# display-board.net
KiCad netlist of a schematic drawn in Altium Designer
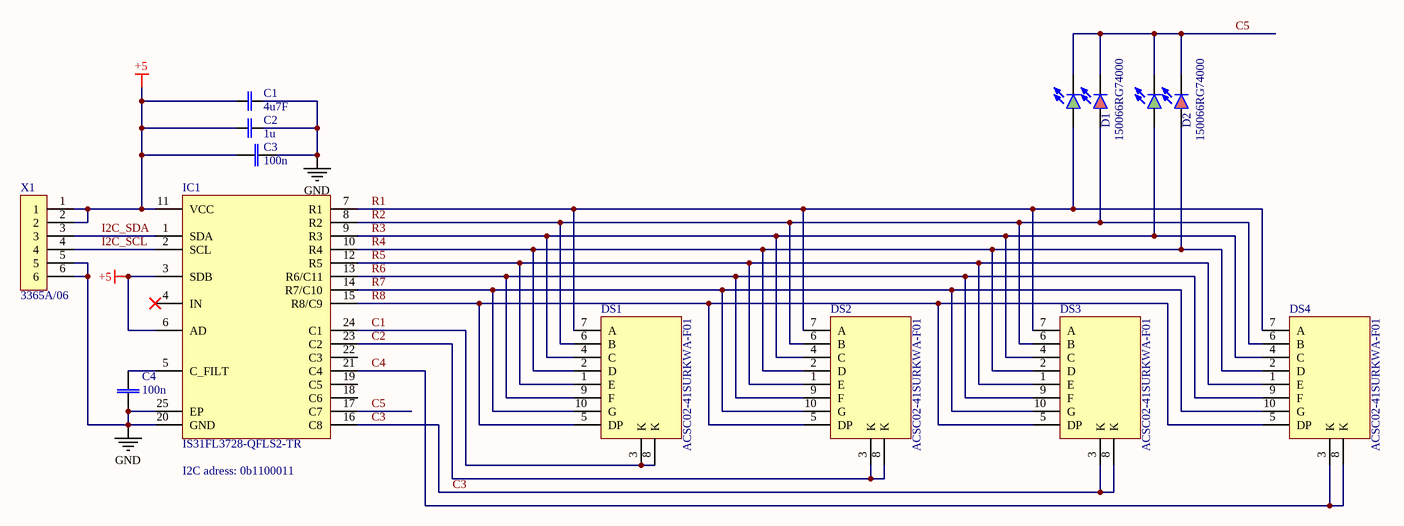
[diagram p0: display-board.SchDoc]

(export (version "E")
  (design (tool "Eeschema 10.0.6"))
  (components
    (comp (ref "C1")
      (value "4u7F")
      (footprint "0805")
      (fields (field (name "PART NUMBER") "000090"))
      (libsource (lib "TychosLibrary") (part "Capacitor"))
    )
    (comp (ref "C2")
      (value "1u")
      (footprint "0603")
      (fields (field (name "PART NUMBER") "000088"))
      (libsource (lib "TychosLibrary") (part "Capacitor"))
    )
    (comp (ref "C3")
      (value "100n")
      (footprint "CAP0402")
      (fields (field (name "MPN") "CL05A104KA5NNNC") (field (name "TOLERANCE") "10%"))
      (libsource (lib "Passive") (part "CL05A104KA5NNNC"))
    )
    (comp (ref "C4")
      (value "100n")
      (footprint "CAP0402")
      (fields (field (name "MPN") "CL05A104KA5NNNC") (field (name "TOLERANCE") "10%"))
      (libsource (lib "Passive") (part "CL05A104KA5NNNC"))
    )
    (comp (ref "D1")
      (value "150066RG74000")
      (footprint "150066RG74000")
      (description "Grün, Rot 520nm Grün, 625nm Rot LED-Indikator - Diskret 3,2V Grün, 2V Rot 0606 (1616 metrisch)")
      (libsource (lib "Schematic") (part "150066RG74000"))
    )
    (comp (ref "D2")
      (value "150066RG74000")
      (footprint "150066RG74000")
      (description "Grün, Rot 520nm Grün, 625nm Rot LED-Indikator - Diskret 3,2V Grün, 2V Rot 0606 (1616 metrisch)")
      (libsource (lib "Schematic") (part "150066RG74000"))
    )
    (comp (ref "DS1")
      (value "ACSC02-41SURKWA-F01")
      (footprint "ACSC02-41SURKWA-F01")
      (libsource (lib "Schematic") (part "ACSC02-41SURKWA-F01"))
    )
    (comp (ref "DS2")
      (value "ACSC02-41SURKWA-F01")
      (footprint "ACSC02-41SURKWA-F01")
      (libsource (lib "Schematic") (part "ACSC02-41SURKWA-F01"))
    )
    (comp (ref "DS3")
      (value "ACSC02-41SURKWA-F01")
      (footprint "ACSC02-41SURKWA-F01")
      (libsource (lib "Schematic") (part "ACSC02-41SURKWA-F01"))
    )
    (comp (ref "DS4")
      (value "ACSC02-41SURKWA-F01")
      (footprint "ACSC02-41SURKWA-F01")
      (libsource (lib "Schematic") (part "ACSC02-41SURKWA-F01"))
    )
    (comp (ref "IC1")
      (value "IS31FL3728-QFLS2-TR")
      (footprint "QFN24_4X4(IS31FL3728)")
      (libsource (lib "Schematic") (part "IS31FL3728-QFLS2-TR"))
    )
    (comp (ref "X1")
      (value "3365A/06")
      (footprint "3M_CBL_RIBN_6X")
      (libsource (lib "Schematic") (part "3365A/06"))
    )
  )
  (nets
    (net (code "1") (name "+5") (class "Default")
      (node (ref "C1") (pin "2") (pinfunction "2_2") (pintype "passive"))
      (node (ref "C2") (pin "2") (pinfunction "2_2") (pintype "passive"))
      (node (ref "C3") (pin "2") (pinfunction "2_2") (pintype "passive"))
      (node (ref "IC1") (pin "11") (pinfunction "VCC_11") (pintype "passive"))
      (node (ref "IC1") (pin "3") (pinfunction "SDB_3") (pintype "passive"))
      (node (ref "IC1") (pin "6") (pinfunction "AD_6") (pintype "passive"))
      (node (ref "X1") (pin "1") (pinfunction "1_1") (pintype "passive"))
      (node (ref "X1") (pin "2") (pinfunction "2_2") (pintype "passive"))
    )
    (net (code "2") (name "/C1") (class "Default")
      (node (ref "DS1") (pin "3") (pinfunction "K_3") (pintype "passive"))
      (node (ref "DS1") (pin "8") (pinfunction "K_8") (pintype "passive"))
      (node (ref "IC1") (pin "24") (pinfunction "C1_24") (pintype "passive"))
    )
    (net (code "3") (name "/C2") (class "Default")
      (node (ref "DS2") (pin "3") (pinfunction "K_3") (pintype "passive"))
      (node (ref "DS2") (pin "8") (pinfunction "K_8") (pintype "passive"))
      (node (ref "IC1") (pin "23") (pinfunction "C2_23") (pintype "passive"))
    )
    (net (code "4") (name "/C3") (class "Default")
      (node (ref "DS3") (pin "3") (pinfunction "K_3") (pintype "passive"))
      (node (ref "DS3") (pin "8") (pinfunction "K_8") (pintype "passive"))
      (node (ref "IC1") (pin "16") (pinfunction "C8_16") (pintype "passive"))
    )
    (net (code "5") (name "/C4") (class "Default")
      (node (ref "DS4") (pin "3") (pinfunction "K_3") (pintype "passive"))
      (node (ref "DS4") (pin "8") (pinfunction "K_8") (pintype "passive"))
      (node (ref "IC1") (pin "21") (pinfunction "C4_21") (pintype "passive"))
    )
    (net (code "6") (name "/C5") (class "Default")
      (node (ref "D1") (pin "1") (pinfunction "1_1") (pintype "passive"))
      (node (ref "D1") (pin "2") (pinfunction "2_2") (pintype "passive"))
      (node (ref "D2") (pin "1") (pinfunction "1_1") (pintype "passive"))
      (node (ref "D2") (pin "2") (pinfunction "2_2") (pintype "passive"))
      (node (ref "IC1") (pin "17") (pinfunction "C7_17") (pintype "passive"))
    )
    (net (code "7") (name "/I2C_SCL") (class "Default")
      (node (ref "IC1") (pin "2") (pinfunction "SCL_2") (pintype "passive"))
      (node (ref "X1") (pin "4") (pinfunction "4_4") (pintype "passive"))
    )
    (net (code "8") (name "/I2C_SDA") (class "Default")
      (node (ref "IC1") (pin "1") (pinfunction "SDA_1") (pintype "passive"))
      (node (ref "X1") (pin "3") (pinfunction "3_3") (pintype "passive"))
    )
    (net (code "9") (name "/R1") (class "Default")
      (node (ref "D1") (pin "3") (pinfunction "3_3") (pintype "passive"))
      (node (ref "DS1") (pin "7") (pinfunction "A_7") (pintype "passive"))
      (node (ref "DS2") (pin "7") (pinfunction "A_7") (pintype "passive"))
      (node (ref "DS3") (pin "7") (pinfunction "A_7") (pintype "passive"))
      (node (ref "DS4") (pin "7") (pinfunction "A_7") (pintype "passive"))
      (node (ref "IC1") (pin "7") (pinfunction "R1_7") (pintype "passive"))
    )
    (net (code "10") (name "/R2") (class "Default")
      (node (ref "D1") (pin "4") (pinfunction "4_4") (pintype "passive"))
      (node (ref "DS1") (pin "6") (pinfunction "B_6") (pintype "passive"))
      (node (ref "DS2") (pin "6") (pinfunction "B_6") (pintype "passive"))
      (node (ref "DS3") (pin "6") (pinfunction "B_6") (pintype "passive"))
      (node (ref "DS4") (pin "6") (pinfunction "B_6") (pintype "passive"))
      (node (ref "IC1") (pin "8") (pinfunction "R2_8") (pintype "passive"))
    )
    (net (code "11") (name "/R3") (class "Default")
      (node (ref "D2") (pin "3") (pinfunction "3_3") (pintype "passive"))
      (node (ref "DS1") (pin "4") (pinfunction "C_4") (pintype "passive"))
      (node (ref "DS2") (pin "4") (pinfunction "C_4") (pintype "passive"))
      (node (ref "DS3") (pin "4") (pinfunction "C_4") (pintype "passive"))
      (node (ref "DS4") (pin "4") (pinfunction "C_4") (pintype "passive"))
      (node (ref "IC1") (pin "9") (pinfunction "R3_9") (pintype "passive"))
    )
    (net (code "12") (name "/R4") (class "Default")
      (node (ref "D2") (pin "4") (pinfunction "4_4") (pintype "passive"))
      (node (ref "DS1") (pin "2") (pinfunction "D_2") (pintype "passive"))
      (node (ref "DS2") (pin "2") (pinfunction "D_2") (pintype "passive"))
      (node (ref "DS3") (pin "2") (pinfunction "D_2") (pintype "passive"))
      (node (ref "DS4") (pin "2") (pinfunction "D_2") (pintype "passive"))
      (node (ref "IC1") (pin "10") (pinfunction "R4_10") (pintype "passive"))
    )
    (net (code "13") (name "/R5") (class "Default")
      (node (ref "DS1") (pin "1") (pinfunction "E_1") (pintype "passive"))
      (node (ref "DS2") (pin "1") (pinfunction "E_1") (pintype "passive"))
      (node (ref "DS3") (pin "1") (pinfunction "E_1") (pintype "passive"))
      (node (ref "DS4") (pin "1") (pinfunction "E_1") (pintype "passive"))
      (node (ref "IC1") (pin "12") (pinfunction "R5_12") (pintype "passive"))
    )
    (net (code "14") (name "/R6") (class "Default")
      (node (ref "DS1") (pin "9") (pinfunction "F_9") (pintype "passive"))
      (node (ref "DS2") (pin "9") (pinfunction "F_9") (pintype "passive"))
      (node (ref "DS3") (pin "9") (pinfunction "F_9") (pintype "passive"))
      (node (ref "DS4") (pin "9") (pinfunction "F_9") (pintype "passive"))
      (node (ref "IC1") (pin "13") (pinfunction "R6/C11_13") (pintype "passive"))
    )
    (net (code "15") (name "/R7") (class "Default")
      (node (ref "DS1") (pin "10") (pinfunction "G_10") (pintype "passive"))
      (node (ref "DS2") (pin "10") (pinfunction "G_10") (pintype "passive"))
      (node (ref "DS3") (pin "10") (pinfunction "G_10") (pintype "passive"))
      (node (ref "DS4") (pin "10") (pinfunction "G_10") (pintype "passive"))
      (node (ref "IC1") (pin "14") (pinfunction "R7/C10_14") (pintype "passive"))
    )
    (net (code "16") (name "/R8") (class "Default")
      (node (ref "DS1") (pin "5") (pinfunction "DP_5") (pintype "passive"))
      (node (ref "DS2") (pin "5") (pinfunction "DP_5") (pintype "passive"))
      (node (ref "DS3") (pin "5") (pinfunction "DP_5") (pintype "passive"))
      (node (ref "DS4") (pin "5") (pinfunction "DP_5") (pintype "passive"))
      (node (ref "IC1") (pin "15") (pinfunction "R8/C9_15") (pintype "passive"))
    )
    (net (code "17") (name "GND") (class "Default")
      (node (ref "C1") (pin "1") (pinfunction "1_1") (pintype "passive"))
      (node (ref "C2") (pin "1") (pinfunction "1_1") (pintype "passive"))
      (node (ref "C3") (pin "1") (pinfunction "1_1") (pintype "passive"))
      (node (ref "C4") (pin "2") (pinfunction "2_2") (pintype "passive"))
      (node (ref "IC1") (pin "20") (pinfunction "GND_20") (pintype "passive"))
      (node (ref "IC1") (pin "25") (pinfunction "EP_25") (pintype "passive"))
      (node (ref "X1") (pin "5") (pinfunction "5_5") (pintype "passive"))
      (node (ref "X1") (pin "6") (pinfunction "6_6") (pintype "passive"))
    )
    (net (code "18") (name "Net-(IC1-C_FILT)") (class "Default")
      (node (ref "C4") (pin "1") (pinfunction "1_1") (pintype "passive"))
      (node (ref "IC1") (pin "5") (pinfunction "C_FILT_5") (pintype "passive"))
    )
    (net (code "19") (name "unconnected-(IC1-C3-Pad22)") (class "Default")
      (node (ref "IC1") (pin "22") (pinfunction "C3_22") (pintype "passive"))
    )
    (net (code "20") (name "unconnected-(IC1-C5-Pad19)") (class "Default")
      (node (ref "IC1") (pin "19") (pinfunction "C5_19") (pintype "passive"))
    )
    (net (code "21") (name "unconnected-(IC1-C6-Pad18)") (class "Default")
      (node (ref "IC1") (pin "18") (pinfunction "C6_18") (pintype "passive"))
    )
    (net (code "22") (name "unconnected-(IC1-IN-Pad4)") (class "Default")
      (node (ref "IC1") (pin "4") (pinfunction "IN_4") (pintype "passive+no_connect"))
    )
  )
)
